# MainBoard.net
KiCad netlist of a schematic drawn in EAGLE
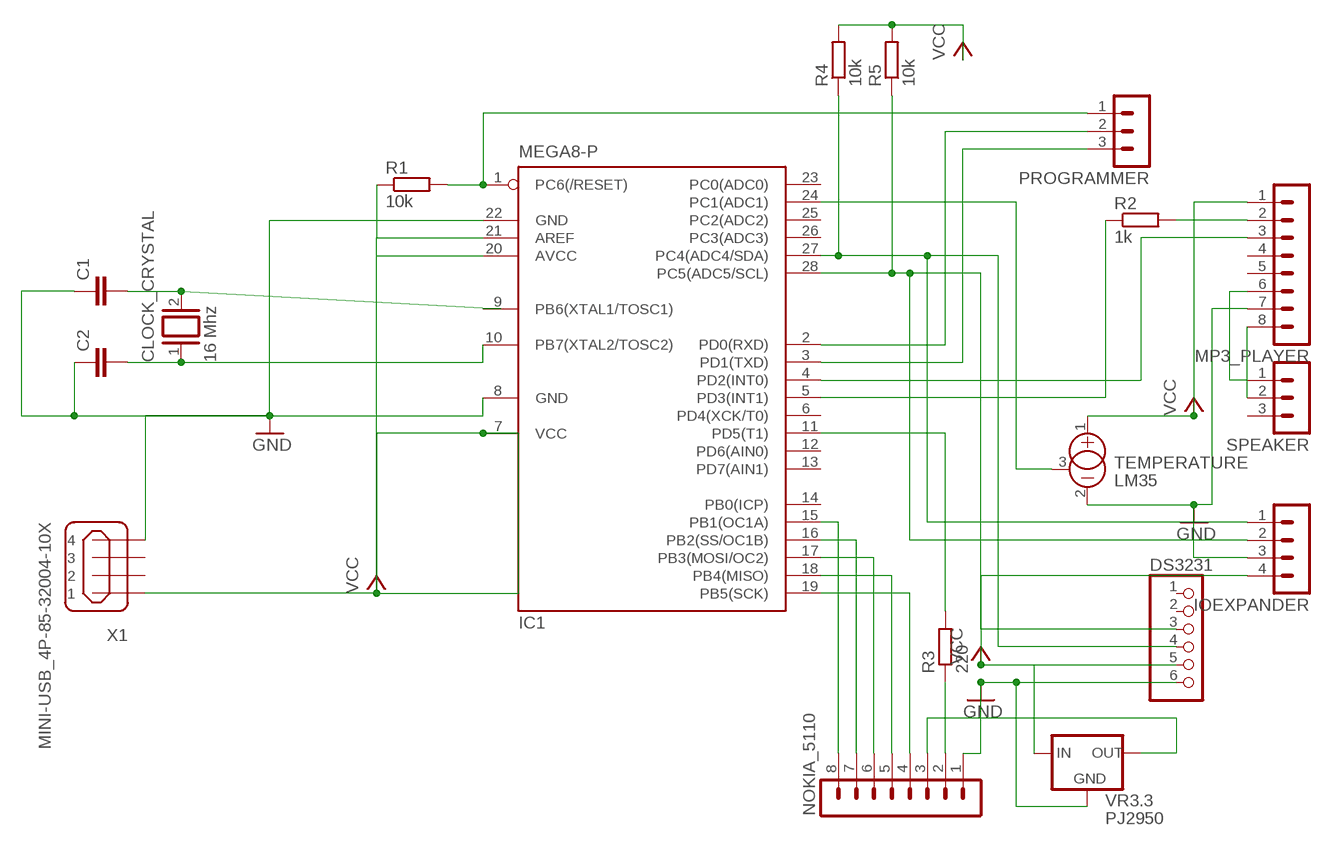
[diagram p0: schematic, sheet 1]

(export (version "E")
  (design (tool "Eeschema 10.0.6"))
  (components
    (comp (ref "C1")
      (value "C2,5-3")
      (footprint "eagle-import:C2.5-3")
      (libsource (lib "eagle-import") (part "C2,5-3"))
    )
    (comp (ref "C2")
      (value "C2,5-3")
      (footprint "eagle-import:C2.5-3")
      (libsource (lib "eagle-import") (part "C2,5-3"))
    )
    (comp (ref "CLOCK_CRYSTAL")
      (value "16 Mhz")
      (footprint "eagle-import:QS")
      (libsource (lib "eagle-import") (part "XTAL/S"))
    )
    (comp (ref "DS3231")
      (value "PINHD-1X6")
      (footprint "eagle-import:1X06")
      (libsource (lib "eagle-import") (part "PINHD-1X6"))
    )
    (comp (ref "IC1")
      (value "MEGA8-P")
      (footprint "eagle-import:DIL28-3")
      (libsource (lib "eagle-import") (part "MEGA8-P"))
    )
    (comp (ref "IOEXPANDER")
      (value "MA04-1")
      (footprint "eagle-import:MA04-1")
      (libsource (lib "eagle-import") (part "MA04-1"))
    )
    (comp (ref "MP3_PLAYER")
      (value "MA08-1W")
      (footprint "eagle-import:MA08-1W")
      (libsource (lib "eagle-import") (part "MA08-1W"))
    )
    (comp (ref "NOKIA_5110")
      (value "MA08-1")
      (footprint "eagle-import:MA08-1")
      (libsource (lib "eagle-import") (part "MA08-1"))
    )
    (comp (ref "PROGRAMMER")
      (value "MA03-1")
      (footprint "eagle-import:MA03-1")
      (libsource (lib "eagle-import") (part "MA03-1"))
    )
    (comp (ref "R1")
      (value "10k")
      (footprint "eagle-import:0204_7")
      (libsource (lib "eagle-import") (part "R-EU_0204/7"))
    )
    (comp (ref "R2")
      (value "1k")
      (footprint "eagle-import:0204_7")
      (libsource (lib "eagle-import") (part "R-EU_0204/7"))
    )
    (comp (ref "R3")
      (value "220")
      (footprint "eagle-import:0204_7")
      (libsource (lib "eagle-import") (part "R-EU_0204/7"))
    )
    (comp (ref "R4")
      (value "10k")
      (footprint "eagle-import:0204_7")
      (libsource (lib "eagle-import") (part "R-EU_0204/7"))
    )
    (comp (ref "R5")
      (value "10k")
      (footprint "eagle-import:0204_7")
      (libsource (lib "eagle-import") (part "R-EU_0204/7"))
    )
    (comp (ref "SPEAKER")
      (value "MA03-1")
      (footprint "eagle-import:MA03-1")
      (libsource (lib "eagle-import") (part "MA03-1"))
    )
    (comp (ref "TEMPERATURE")
      (value "LM35")
      (footprint "eagle-import:TO92")
      (libsource (lib "eagle-import") (part "AD590ZR"))
    )
    (comp (ref "VR3.3")
      (value "PJ2950")
      (footprint "eagle-import:78LXX")
      (libsource (lib "eagle-import") (part "78LXX"))
    )
    (comp (ref "X1")
      (value "MINI-USB_4P-85-32004-10X")
      (footprint "eagle-import:85-32004-10X")
      (libsource (lib "eagle-import") (part "MINI-USB_4P-85-32004-10X"))
    )
  )
  (nets
    (net (code "1") (name "GND") (class "Default")
      (node (ref "C1") (pin "1") (pinfunction "1_1") (pintype "passive"))
      (node (ref "C2") (pin "1") (pinfunction "1_1") (pintype "passive"))
      (node (ref "DS3231") (pin "6") (pinfunction "6_6") (pintype "passive"))
      (node (ref "IC1") (pin "22") (pinfunction "GND_22") (pintype "power_in"))
      (node (ref "IC1") (pin "8") (pinfunction "GND_8") (pintype "power_in"))
      (node (ref "IOEXPANDER") (pin "3") (pinfunction "3_3") (pintype "passive"))
      (node (ref "MP3_PLAYER") (pin "7") (pinfunction "7_7") (pintype "passive"))
      (node (ref "NOKIA_5110") (pin "1") (pinfunction "1_1") (pintype "passive"))
      (node (ref "TEMPERATURE") (pin "2") (pinfunction "-_2") (pintype "input"))
      (node (ref "VR3.3") (pin "GND") (pinfunction "GND_GND") (pintype "input"))
      (node (ref "X1") (pin "4") (pinfunction "4_4") (pintype "passive"))
    )
    (net (code "2") (name "Net-(IC1-PB1(OC1A))") (class "Default")
      (node (ref "IC1") (pin "15") (pinfunction "PB1(OC1A)_15") (pintype "bidirectional"))
      (node (ref "NOKIA_5110") (pin "8") (pinfunction "8_8") (pintype "passive"))
    )
    (net (code "3") (name "Net-(IC1-PB2(SS{slash}OC1B))") (class "Default")
      (node (ref "IC1") (pin "16") (pinfunction "PB2(SS/OC1B)_16") (pintype "bidirectional"))
      (node (ref "NOKIA_5110") (pin "7") (pinfunction "7_7") (pintype "passive"))
    )
    (net (code "4") (name "Net-(IC1-PB3(MOSI{slash}OC2))") (class "Default")
      (node (ref "IC1") (pin "17") (pinfunction "PB3(MOSI/OC2)_17") (pintype "bidirectional"))
      (node (ref "NOKIA_5110") (pin "6") (pinfunction "6_6") (pintype "passive"))
    )
    (net (code "5") (name "Net-(IC1-PB4(MISO))") (class "Default")
      (node (ref "IC1") (pin "18") (pinfunction "PB4(MISO)_18") (pintype "bidirectional"))
      (node (ref "NOKIA_5110") (pin "5") (pinfunction "5_5") (pintype "passive"))
    )
    (net (code "6") (name "Net-(IC1-PB5(SCK))") (class "Default")
      (node (ref "IC1") (pin "19") (pinfunction "PB5(SCK)_19") (pintype "bidirectional"))
      (node (ref "NOKIA_5110") (pin "4") (pinfunction "4_4") (pintype "passive"))
    )
    (net (code "7") (name "Net-(IC1-PB6(XTAL1{slash}TOSC1))") (class "Default")
      (node (ref "C1") (pin "2") (pinfunction "2_2") (pintype "passive"))
      (node (ref "CLOCK_CRYSTAL") (pin "2") (pinfunction "2_2") (pintype "passive"))
      (node (ref "IC1") (pin "9") (pinfunction "PB6(XTAL1/TOSC1)_9") (pintype "bidirectional"))
    )
    (net (code "8") (name "Net-(IC1-PB7(XTAL2{slash}TOSC2))") (class "Default")
      (node (ref "C2") (pin "2") (pinfunction "2_2") (pintype "passive"))
      (node (ref "CLOCK_CRYSTAL") (pin "1") (pinfunction "1_1") (pintype "passive"))
      (node (ref "IC1") (pin "10") (pinfunction "PB7(XTAL2/TOSC2)_10") (pintype "bidirectional"))
    )
    (net (code "9") (name "Net-(IC1-PC1(ADC1))") (class "Default")
      (node (ref "IC1") (pin "24") (pinfunction "PC1(ADC1)_24") (pintype "bidirectional"))
      (node (ref "TEMPERATURE") (pin "3") (pinfunction "CAN_3") (pintype "passive"))
    )
    (net (code "10") (name "Net-(IC1-PC4(ADC4{slash}SDA))") (class "Default")
      (node (ref "DS3231") (pin "4") (pinfunction "4_4") (pintype "passive"))
      (node (ref "IC1") (pin "27") (pinfunction "PC4(ADC4/SDA)_27") (pintype "bidirectional"))
      (node (ref "IOEXPANDER") (pin "1") (pinfunction "1_1") (pintype "passive"))
      (node (ref "R4") (pin "1") (pinfunction "1_1") (pintype "passive"))
    )
    (net (code "11") (name "Net-(IC1-PC5(ADC5{slash}SCL))") (class "Default")
      (node (ref "DS3231") (pin "3") (pinfunction "3_3") (pintype "passive"))
      (node (ref "IC1") (pin "28") (pinfunction "PC5(ADC5/SCL)_28") (pintype "bidirectional"))
      (node (ref "IOEXPANDER") (pin "2") (pinfunction "2_2") (pintype "passive"))
      (node (ref "R5") (pin "1") (pinfunction "1_1") (pintype "passive"))
    )
    (net (code "12") (name "Net-(IC1-PC6({slash}RESET))") (class "Default")
      (node (ref "IC1") (pin "1") (pinfunction "PC6(/RESET)_1") (pintype "bidirectional"))
      (node (ref "PROGRAMMER") (pin "1") (pinfunction "1_1") (pintype "passive"))
      (node (ref "R1") (pin "2") (pinfunction "2_2") (pintype "passive"))
    )
    (net (code "13") (name "Net-(IC1-PD0(RXD))") (class "Default")
      (node (ref "IC1") (pin "2") (pinfunction "PD0(RXD)_2") (pintype "bidirectional"))
      (node (ref "PROGRAMMER") (pin "2") (pinfunction "2_2") (pintype "passive"))
    )
    (net (code "14") (name "Net-(IC1-PD1(TXD))") (class "Default")
      (node (ref "IC1") (pin "3") (pinfunction "PD1(TXD)_3") (pintype "bidirectional"))
      (node (ref "PROGRAMMER") (pin "3") (pinfunction "3_3") (pintype "passive"))
    )
    (net (code "15") (name "Net-(IC1-PD2(INT0))") (class "Default")
      (node (ref "IC1") (pin "4") (pinfunction "PD2(INT0)_4") (pintype "bidirectional"))
      (node (ref "MP3_PLAYER") (pin "3") (pinfunction "3_3") (pintype "passive"))
    )
    (net (code "16") (name "Net-(IC1-PD3(INT1))") (class "Default")
      (node (ref "IC1") (pin "5") (pinfunction "PD3(INT1)_5") (pintype "bidirectional"))
      (node (ref "R2") (pin "1") (pinfunction "1_1") (pintype "passive"))
    )
    (net (code "17") (name "Net-(IC1-PD5(T1))") (class "Default")
      (node (ref "IC1") (pin "11") (pinfunction "PD5(T1)_11") (pintype "bidirectional"))
      (node (ref "R3") (pin "2") (pinfunction "2_2") (pintype "passive"))
    )
    (net (code "18") (name "Net-(MP3_PLAYER-Pad2)") (class "Default")
      (node (ref "MP3_PLAYER") (pin "2") (pinfunction "2_2") (pintype "passive"))
      (node (ref "R2") (pin "2") (pinfunction "2_2") (pintype "passive"))
    )
    (net (code "19") (name "Net-(MP3_PLAYER-Pad6)") (class "Default")
      (node (ref "MP3_PLAYER") (pin "6") (pinfunction "6_6") (pintype "passive"))
      (node (ref "SPEAKER") (pin "1") (pinfunction "1_1") (pintype "passive"))
    )
    (net (code "20") (name "Net-(MP3_PLAYER-Pad8)") (class "Default")
      (node (ref "MP3_PLAYER") (pin "8") (pinfunction "8_8") (pintype "passive"))
      (node (ref "SPEAKER") (pin "2") (pinfunction "2_2") (pintype "passive"))
    )
    (net (code "21") (name "Net-(NOKIA_5110-Pad2)") (class "Default")
      (node (ref "NOKIA_5110") (pin "2") (pinfunction "2_2") (pintype "passive"))
      (node (ref "R3") (pin "1") (pinfunction "1_1") (pintype "passive"))
    )
    (net (code "22") (name "Net-(NOKIA_5110-Pad3)") (class "Default")
      (node (ref "NOKIA_5110") (pin "3") (pinfunction "3_3") (pintype "passive"))
      (node (ref "VR3.3") (pin "OUT") (pinfunction "OUT_OUT") (pintype "passive"))
    )
    (net (code "23") (name "VCC") (class "Default")
      (node (ref "DS3231") (pin "5") (pinfunction "5_5") (pintype "passive"))
      (node (ref "IC1") (pin "20") (pinfunction "AVCC_20") (pintype "power_in"))
      (node (ref "IC1") (pin "21") (pinfunction "AREF_21") (pintype "passive"))
      (node (ref "IC1") (pin "7") (pinfunction "VCC_7") (pintype "power_in"))
      (node (ref "IOEXPANDER") (pin "4") (pinfunction "4_4") (pintype "passive"))
      (node (ref "MP3_PLAYER") (pin "1") (pinfunction "1_1") (pintype "passive"))
      (node (ref "R1") (pin "1") (pinfunction "1_1") (pintype "passive"))
      (node (ref "R4") (pin "2") (pinfunction "2_2") (pintype "passive"))
      (node (ref "R5") (pin "2") (pinfunction "2_2") (pintype "passive"))
      (node (ref "TEMPERATURE") (pin "1") (pinfunction "+_1") (pintype "input"))
      (node (ref "VR3.3") (pin "IN") (pinfunction "IN_IN") (pintype "input"))
      (node (ref "X1") (pin "1") (pinfunction "1_1") (pintype "passive"))
    )
    (net (code "24") (name "unconnected-(DS3231-Pad1)") (class "Default")
      (node (ref "DS3231") (pin "1") (pinfunction "1_1") (pintype "passive"))
    )
    (net (code "25") (name "unconnected-(DS3231-Pad2)") (class "Default")
      (node (ref "DS3231") (pin "2") (pinfunction "2_2") (pintype "passive"))
    )
    (net (code "26") (name "unconnected-(IC1-PB0(ICP)-Pad14)") (class "Default")
      (node (ref "IC1") (pin "14") (pinfunction "PB0(ICP)_14") (pintype "bidirectional"))
    )
    (net (code "27") (name "unconnected-(IC1-PC0(ADC0)-Pad23)") (class "Default")
      (node (ref "IC1") (pin "23") (pinfunction "PC0(ADC0)_23") (pintype "bidirectional"))
    )
    (net (code "28") (name "unconnected-(IC1-PC2(ADC2)-Pad25)") (class "Default")
      (node (ref "IC1") (pin "25") (pinfunction "PC2(ADC2)_25") (pintype "bidirectional"))
    )
    (net (code "29") (name "unconnected-(IC1-PC3(ADC3)-Pad26)") (class "Default")
      (node (ref "IC1") (pin "26") (pinfunction "PC3(ADC3)_26") (pintype "bidirectional"))
    )
    (net (code "30") (name "unconnected-(IC1-PD4(XCK{slash}T0)-Pad6)") (class "Default")
      (node (ref "IC1") (pin "6") (pinfunction "PD4(XCK/T0)_6") (pintype "bidirectional"))
    )
    (net (code "31") (name "unconnected-(IC1-PD6(AIN0)-Pad12)") (class "Default")
      (node (ref "IC1") (pin "12") (pinfunction "PD6(AIN0)_12") (pintype "bidirectional"))
    )
    (net (code "32") (name "unconnected-(IC1-PD7(AIN1)-Pad13)") (class "Default")
      (node (ref "IC1") (pin "13") (pinfunction "PD7(AIN1)_13") (pintype "bidirectional"))
    )
    (net (code "33") (name "unconnected-(MP3_PLAYER-Pad4)") (class "Default")
      (node (ref "MP3_PLAYER") (pin "4") (pinfunction "4_4") (pintype "passive"))
    )
    (net (code "34") (name "unconnected-(MP3_PLAYER-Pad5)") (class "Default")
      (node (ref "MP3_PLAYER") (pin "5") (pinfunction "5_5") (pintype "passive"))
    )
    (net (code "35") (name "unconnected-(SPEAKER-Pad3)") (class "Default")
      (node (ref "SPEAKER") (pin "3") (pinfunction "3_3") (pintype "passive"))
    )
    (net (code "36") (name "unconnected-(X1-Pad2)") (class "Default")
      (node (ref "X1") (pin "2") (pinfunction "2_2") (pintype "passive"))
    )
    (net (code "37") (name "unconnected-(X1-Pad3)") (class "Default")
      (node (ref "X1") (pin "3") (pinfunction "3_3") (pintype "passive"))
    )
  )
)
